# joey.net
KiCad netlist of a schematic drawn in EAGLE
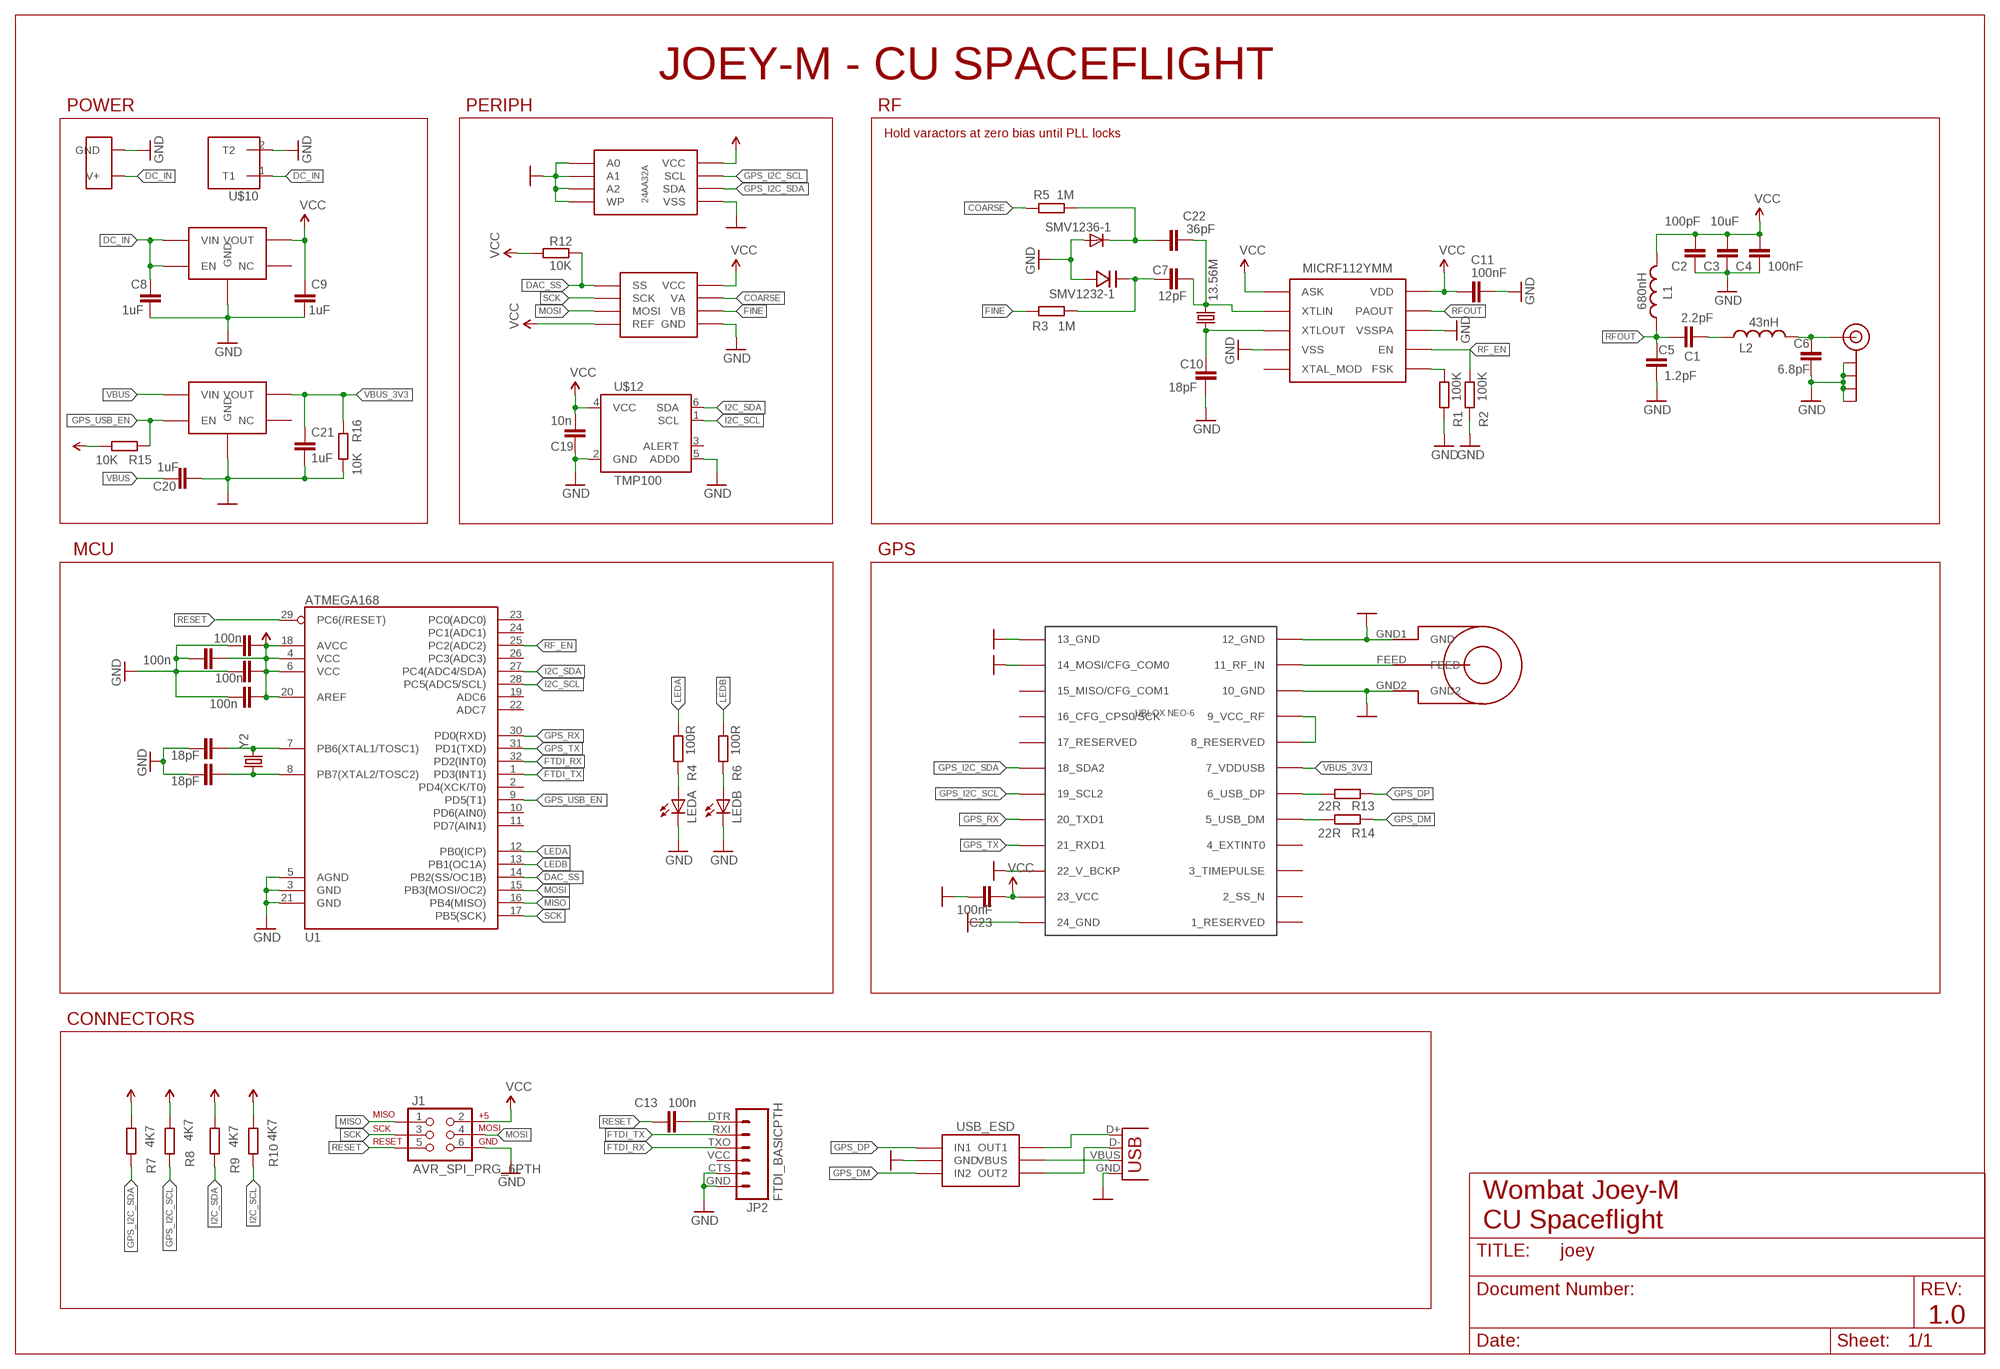
[diagram p0: schematic, sheet 1]

(export (version "E")
  (design (tool "Eeschema 10.0.6"))
  (components
    (comp (ref "C1")
      (value "2.2pF")
      (footprint "eagle-import:C0603")
      (libsource (lib "eagle-import") (part "C-EUC0603"))
    )
    (comp (ref "C2")
      (value "100pF")
      (footprint "eagle-import:C0603")
      (libsource (lib "eagle-import") (part "C-EUC0603"))
    )
    (comp (ref "C3")
      (value "10uF")
      (footprint "eagle-import:C0603")
      (libsource (lib "eagle-import") (part "C-EUC0603"))
    )
    (comp (ref "C4")
      (value "100nF")
      (footprint "eagle-import:C0603")
      (libsource (lib "eagle-import") (part "C-EUC0603"))
    )
    (comp (ref "C5")
      (value "1.2pF")
      (footprint "eagle-import:C0603")
      (libsource (lib "eagle-import") (part "C-EUC0603"))
    )
    (comp (ref "C6")
      (value "6.8pF")
      (footprint "eagle-import:C0603")
      (libsource (lib "eagle-import") (part "C-EUC0603"))
    )
    (comp (ref "C7")
      (value "12pF")
      (footprint "eagle-import:C0603")
      (libsource (lib "eagle-import") (part "C-EUC0603"))
    )
    (comp (ref "C8")
      (value "1uF")
      (footprint "eagle-import:C0603")
      (libsource (lib "eagle-import") (part "C-EUC0603"))
    )
    (comp (ref "C9")
      (value "1uF")
      (footprint "eagle-import:C0603")
      (libsource (lib "eagle-import") (part "C-EUC0603"))
    )
    (comp (ref "C10")
      (value "18pF")
      (footprint "eagle-import:C0603")
      (libsource (lib "eagle-import") (part "C-EUC0603"))
    )
    (comp (ref "C11")
      (value "100nF")
      (footprint "eagle-import:C0603")
      (libsource (lib "eagle-import") (part "C-EUC0603"))
    )
    (comp (ref "C12")
      (value "100n")
      (footprint "eagle-import:C0603")
      (libsource (lib "eagle-import") (part "C-EUC0603"))
    )
    (comp (ref "C13")
      (value "100n")
      (footprint "eagle-import:C0603")
      (libsource (lib "eagle-import") (part "C-EUC0603"))
    )
    (comp (ref "C14")
      (value "100n")
      (footprint "eagle-import:C0603")
      (libsource (lib "eagle-import") (part "C-EUC0603"))
    )
    (comp (ref "C15")
      (value "100n")
      (footprint "eagle-import:C0603")
      (libsource (lib "eagle-import") (part "C-EUC0603"))
    )
    (comp (ref "C16")
      (value "100n")
      (footprint "eagle-import:C0603")
      (libsource (lib "eagle-import") (part "C-EUC0603"))
    )
    (comp (ref "C17")
      (value "18pF")
      (footprint "eagle-import:C0603")
      (libsource (lib "eagle-import") (part "C-EUC0603"))
    )
    (comp (ref "C18")
      (value "18pF")
      (footprint "eagle-import:C0603")
      (libsource (lib "eagle-import") (part "C-EUC0603"))
    )
    (comp (ref "C19")
      (value "10n")
      (footprint "eagle-import:C0603")
      (libsource (lib "eagle-import") (part "C-EUC0603"))
    )
    (comp (ref "C20")
      (value "1uF")
      (footprint "eagle-import:C0603")
      (libsource (lib "eagle-import") (part "C-EUC0603"))
    )
    (comp (ref "C21")
      (value "1uF")
      (footprint "eagle-import:C0603")
      (libsource (lib "eagle-import") (part "C-EUC0603"))
    )
    (comp (ref "C22")
      (value "36pF")
      (footprint "eagle-import:C0603")
      (libsource (lib "eagle-import") (part "C-EUC0603"))
    )
    (comp (ref "C23")
      (value "100nF")
      (footprint "eagle-import:C0603")
      (libsource (lib "eagle-import") (part "C-EUC0603"))
    )
    (comp (ref "J1")
      (value "AVR_SPI_PRG_6PTH")
      (footprint "eagle-import:2X3")
      (libsource (lib "eagle-import") (part "AVR_SPI_PRG_6PTH"))
    )
    (comp (ref "JP2")
      (value "FTDI_BASICPTH")
      (footprint "eagle-import:FTDI_BASIC")
      (libsource (lib "eagle-import") (part "FTDI_BASICPTH"))
    )
    (comp (ref "L1")
      (value "680nH")
      (footprint "eagle-import:0603")
      (libsource (lib "eagle-import") (part "INDUCTOR0603"))
    )
    (comp (ref "L2")
      (value "43nH")
      (footprint "eagle-import:C0402")
      (libsource (lib "eagle-import") (part "INDUCTOR0402"))
    )
    (comp (ref "LEDA")
      (value "LED0603")
      (footprint "eagle-import:LED-0603")
      (libsource (lib "eagle-import") (part "LED0603"))
    )
    (comp (ref "LEDB")
      (value "LED0603")
      (footprint "eagle-import:LED-0603")
      (libsource (lib "eagle-import") (part "LED0603"))
    )
    (comp (ref "R1")
      (value "100K")
      (footprint "eagle-import:R0603")
      (libsource (lib "eagle-import") (part "R-EU_R0603"))
    )
    (comp (ref "R2")
      (value "100K")
      (footprint "eagle-import:R0603")
      (libsource (lib "eagle-import") (part "R-EU_R0603"))
    )
    (comp (ref "R3")
      (value "1M")
      (footprint "eagle-import:R0603")
      (libsource (lib "eagle-import") (part "R-EU_R0603"))
    )
    (comp (ref "R4")
      (value "100R")
      (footprint "eagle-import:R0603")
      (libsource (lib "eagle-import") (part "R-EU_R0603"))
    )
    (comp (ref "R5")
      (value "1M")
      (footprint "eagle-import:R0603")
      (libsource (lib "eagle-import") (part "R-EU_R0603"))
    )
    (comp (ref "R6")
      (value "100R")
      (footprint "eagle-import:R0603")
      (libsource (lib "eagle-import") (part "R-EU_R0603"))
    )
    (comp (ref "R7")
      (value "4K7")
      (footprint "eagle-import:R0603")
      (libsource (lib "eagle-import") (part "R-EU_R0603"))
    )
    (comp (ref "R8")
      (value "4K7")
      (footprint "eagle-import:R0603")
      (libsource (lib "eagle-import") (part "R-EU_R0603"))
    )
    (comp (ref "R9")
      (value "4K7")
      (footprint "eagle-import:R0603")
      (libsource (lib "eagle-import") (part "R-EU_R0603"))
    )
    (comp (ref "R10")
      (value "4K7")
      (footprint "eagle-import:R0603")
      (libsource (lib "eagle-import") (part "R-EU_R0603"))
    )
    (comp (ref "R12")
      (value "10K")
      (footprint "eagle-import:R0603")
      (libsource (lib "eagle-import") (part "R-EU_R0603"))
    )
    (comp (ref "R13")
      (value "22R")
      (footprint "eagle-import:R0603")
      (libsource (lib "eagle-import") (part "R-EU_R0603"))
    )
    (comp (ref "R14")
      (value "22R")
      (footprint "eagle-import:R0603")
      (libsource (lib "eagle-import") (part "R-EU_R0603"))
    )
    (comp (ref "R15")
      (value "10K")
      (footprint "eagle-import:R0603")
      (libsource (lib "eagle-import") (part "R-EU_R0603"))
    )
    (comp (ref "R16")
      (value "10K")
      (footprint "eagle-import:R0603")
      (libsource (lib "eagle-import") (part "R-EU_R0603"))
    )
    (comp (ref "SMV1232-1")
      (value "SMV1247-VARACTOR")
      (footprint "eagle-import:SMV1247-VARACTOR-SC-79")
      (libsource (lib "eagle-import") (part "SMV1247-VARACTOR"))
    )
    (comp (ref "SMV1236-1")
      (value "DIODESOD")
      (footprint "eagle-import:SOD-323")
      (libsource (lib "eagle-import") (part "DIODESOD"))
    )
    (comp (ref "U$1")
      (value "MICRF112")
      (footprint "eagle-import:MICRF112-MSOP10")
      (libsource (lib "eagle-import") (part "MICRF112"))
    )
    (comp (ref "U$2")
      (value "SARANTEL-SR1202")
      (footprint "eagle-import:SARANTEL-SR1202")
      (libsource (lib "eagle-import") (part "SARANTEL-SR1202"))
    )
    (comp (ref "U$3")
      (value "UBLOX_NEO-6")
      (footprint "eagle-import:UBLOX_NEO-6P")
      (libsource (lib "eagle-import") (part "UBLOX_NEO-6"))
    )
    (comp (ref "U$4")
      (value "ADP122AUJZ-3V3REG-5TSOT")
      (footprint "eagle-import:SOT23-5L")
      (libsource (lib "eagle-import") (part "ADP122AUJZ-3V3REG-5TSOT"))
    )
    (comp (ref "U$5")
      (value "JST_SMTSIDE")
      (footprint "eagle-import:JST_CONN_SMD")
      (libsource (lib "eagle-import") (part "JST_SMTSIDE"))
    )
    (comp (ref "U$6")
      (value "I2C_EEPROM_24AA32A")
      (footprint "eagle-import:MSOP8")
      (libsource (lib "eagle-import") (part "I2C_EEPROM_24AA32A"))
    )
    (comp (ref "U$7")
      (value "SMA_END_19-70-TGG")
      (footprint "eagle-import:SMA_END_19-70-TGG")
      (libsource (lib "eagle-import") (part "SMA_END_19-70-TGG"))
    )
    (comp (ref "U$8")
      (value "LTC2602_16BIT_DUALDAC")
      (footprint "eagle-import:MSOP8")
      (libsource (lib "eagle-import") (part "LTC2602_16BIT_DUALDAC"))
    )
    (comp (ref "U$9")
      (value "ADP122AUJZ-3V3REG-5TSOT")
      (footprint "eagle-import:SOT23-5L")
      (libsource (lib "eagle-import") (part "ADP122AUJZ-3V3REG-5TSOT"))
    )
    (comp (ref "U$10")
      (value "TE_CONN_TERMBLK")
      (footprint "eagle-import:10A_TECONN_TERMBLK")
      (libsource (lib "eagle-import") (part "TE_CONN_TERMBLK"))
    )
    (comp (ref "U$12")
      (value "TMP100")
      (footprint "eagle-import:SOT23-6")
      (libsource (lib "eagle-import") (part "TMP100"))
    )
    (comp (ref "U1")
      (value "ATMEGA168")
      (footprint "eagle-import:TQFP32-08")
      (libsource (lib "eagle-import") (part "ATMEGA168"))
    )
    (comp (ref "USB_ESD")
      (value "USB_ESD_PROT_USBLC6")
      (footprint "eagle-import:SOT23-6")
      (libsource (lib "eagle-import") (part "USB_ESD_PROT_USBLC6"))
    )
    (comp (ref "X1")
      (value "USB-MICROB")
      (footprint "eagle-import:USB-MICROB")
      (libsource (lib "eagle-import") (part "USB-MICROB"))
    )
    (comp (ref "Y1")
      (value "13.56M")
      (footprint "eagle-import:CRYSTAL-SMD-5X3")
      (libsource (lib "eagle-import") (part "CRYSTAL5X3"))
    )
    (comp (ref "Y2")
      (value "CRYSTAL5X3")
      (footprint "eagle-import:CRYSTAL-SMD-5X3")
      (libsource (lib "eagle-import") (part "CRYSTAL5X3"))
    )
  )
  (nets
    (net (code "1") (name "COARSE") (class "Default")
      (node (ref "R5") (pin "1") (pinfunction "1_1") (pintype "passive"))
      (node (ref "U$8") (pin "8") (pinfunction "VA_8") (pintype "bidirectional"))
    )
    (net (code "2") (name "DAC_SS") (class "Default")
      (node (ref "R12") (pin "2") (pinfunction "2_2") (pintype "passive"))
      (node (ref "U$8") (pin "1") (pinfunction "SS_1") (pintype "bidirectional"))
      (node (ref "U1") (pin "14") (pinfunction "PB2(SS/OC1B)_14") (pintype "bidirectional"))
    )
    (net (code "3") (name "DC_IN") (class "Default")
      (node (ref "C8") (pin "2") (pinfunction "2_2") (pintype "passive"))
      (node (ref "U$10") (pin "1") (pinfunction "T1_1") (pintype "bidirectional"))
      (node (ref "U$4") (pin "1") (pinfunction "VIN_1") (pintype "bidirectional"))
      (node (ref "U$4") (pin "3") (pinfunction "EN_3") (pintype "bidirectional"))
      (node (ref "U$5") (pin "VBATT") (pinfunction "V+_VBATT") (pintype "bidirectional"))
    )
    (net (code "4") (name "FINE") (class "Default")
      (node (ref "R3") (pin "2") (pinfunction "2_2") (pintype "passive"))
      (node (ref "U$8") (pin "5") (pinfunction "VB_5") (pintype "bidirectional"))
    )
    (net (code "5") (name "FTDI_RX") (class "Default")
      (node (ref "JP2") (pin "TXO") (pinfunction "3_TXO") (pintype "passive"))
      (node (ref "U1") (pin "32") (pinfunction "PD2(INT0)_32") (pintype "bidirectional"))
    )
    (net (code "6") (name "FTDI_TX") (class "Default")
      (node (ref "JP2") (pin "RXI") (pinfunction "2_RXI") (pintype "passive"))
      (node (ref "U1") (pin "1") (pinfunction "PD3(INT1)_1") (pintype "bidirectional"))
    )
    (net (code "7") (name "GND") (class "Default")
      (node (ref "C10") (pin "1") (pinfunction "1_1") (pintype "passive"))
      (node (ref "C11") (pin "1") (pinfunction "1_1") (pintype "passive"))
      (node (ref "C12") (pin "2") (pinfunction "2_2") (pintype "passive"))
      (node (ref "C14") (pin "1") (pinfunction "1_1") (pintype "passive"))
      (node (ref "C15") (pin "1") (pinfunction "1_1") (pintype "passive"))
      (node (ref "C16") (pin "1") (pinfunction "1_1") (pintype "passive"))
      (node (ref "C17") (pin "2") (pinfunction "2_2") (pintype "passive"))
      (node (ref "C18") (pin "2") (pinfunction "2_2") (pintype "passive"))
      (node (ref "C19") (pin "1") (pinfunction "1_1") (pintype "passive"))
      (node (ref "C2") (pin "1") (pinfunction "1_1") (pintype "passive"))
      (node (ref "C20") (pin "1") (pinfunction "1_1") (pintype "passive"))
      (node (ref "C21") (pin "1") (pinfunction "1_1") (pintype "passive"))
      (node (ref "C23") (pin "1") (pinfunction "1_1") (pintype "passive"))
      (node (ref "C3") (pin "1") (pinfunction "1_1") (pintype "passive"))
      (node (ref "C4") (pin "1") (pinfunction "1_1") (pintype "passive"))
      (node (ref "C5") (pin "1") (pinfunction "1_1") (pintype "passive"))
      (node (ref "C6") (pin "1") (pinfunction "1_1") (pintype "passive"))
      (node (ref "C8") (pin "1") (pinfunction "1_1") (pintype "passive"))
      (node (ref "C9") (pin "1") (pinfunction "1_1") (pintype "passive"))
      (node (ref "J1") (pin "6") (pinfunction "6_6") (pintype "passive"))
      (node (ref "JP2") (pin "CTS") (pinfunction "5_CTS") (pintype "passive"))
      (node (ref "JP2") (pin "GND") (pinfunction "6_GND") (pintype "passive"))
      (node (ref "LEDA") (pin "C") (pinfunction "C_C") (pintype "passive"))
      (node (ref "LEDB") (pin "C") (pinfunction "C_C") (pintype "passive"))
      (node (ref "R1") (pin "1") (pinfunction "1_1") (pintype "passive"))
      (node (ref "R16") (pin "2") (pinfunction "2_2") (pintype "passive"))
      (node (ref "R2") (pin "1") (pinfunction "1_1") (pintype "passive"))
      (node (ref "SMV1232-1") (pin "AN") (pinfunction "ANODE_AN") (pintype "bidirectional"))
      (node (ref "SMV1236-1") (pin "2") (pinfunction "A_2") (pintype "passive"))
      (node (ref "U$1") (pin "VSS") (pinfunction "VSS_VSS") (pintype "bidirectional"))
      (node (ref "U$1") (pin "VSSPA") (pinfunction "VSSPA_VSSPA") (pintype "bidirectional"))
      (node (ref "U$10") (pin "2") (pinfunction "T2_2") (pintype "bidirectional"))
      (node (ref "U$12") (pin "2") (pinfunction "GND_2") (pintype "bidirectional"))
      (node (ref "U$12") (pin "5") (pinfunction "ADD0_5") (pintype "bidirectional"))
      (node (ref "U$2") (pin "GND1") (pinfunction "GND_GND1") (pintype "bidirectional"))
      (node (ref "U$2") (pin "GND2") (pinfunction "GND2_GND2") (pintype "bidirectional"))
      (node (ref "U$3") (pin "10_GND") (pinfunction "10_GND_10_GND") (pintype "bidirectional"))
      (node (ref "U$3") (pin "12_GND") (pinfunction "12_GND_12_GND") (pintype "bidirectional"))
      (node (ref "U$3") (pin "13_GND") (pinfunction "13_GND_13_GND") (pintype "bidirectional"))
      (node (ref "U$3") (pin "14_MOSI/CFG_COM0") (pinfunction "14_MOSI/CFG_COM0_14_MOSI/CFG_COM0") (pintype "bidirectional"))
      (node (ref "U$3") (pin "22_V_BCKP") (pinfunction "22_V_BCKP_22_V_BCKP") (pintype "bidirectional"))
      (node (ref "U$3") (pin "24_GND") (pinfunction "24_GND_24_GND") (pintype "bidirectional"))
      (node (ref "U$4") (pin "2") (pinfunction "GND_2") (pintype "bidirectional"))
      (node (ref "U$5") (pin "GND") (pinfunction "GND_GND") (pintype "bidirectional"))
      (node (ref "U$6") (pin "1") (pinfunction "A0_1") (pintype "bidirectional"))
      (node (ref "U$6") (pin "2") (pinfunction "A1_2") (pintype "bidirectional"))
      (node (ref "U$6") (pin "3") (pinfunction "A2_3") (pintype "bidirectional"))
      (node (ref "U$6") (pin "4") (pinfunction "VSS_4") (pintype "bidirectional"))
      (node (ref "U$6") (pin "7") (pinfunction "WP_7") (pintype "bidirectional"))
      (node (ref "U$7") (pin "GND1") (pinfunction "GND_GND1") (pintype "bidirectional"))
      (node (ref "U$7") (pin "GND2") (pinfunction "GND_GND2") (pintype "bidirectional"))
      (node (ref "U$7") (pin "GND3") (pinfunction "GND_GND3") (pintype "bidirectional"))
      (node (ref "U$7") (pin "GND4") (pinfunction "GND_GND4") (pintype "bidirectional"))
      (node (ref "U$8") (pin "7") (pinfunction "GND_7") (pintype "bidirectional"))
      (node (ref "U$9") (pin "2") (pinfunction "GND_2") (pintype "bidirectional"))
      (node (ref "U1") (pin "21") (pinfunction "GND_21") (pintype "bidirectional"))
      (node (ref "U1") (pin "3") (pinfunction "GND_3") (pintype "bidirectional"))
      (node (ref "U1") (pin "5") (pinfunction "AGND_5") (pintype "bidirectional"))
      (node (ref "USB_ESD") (pin "2") (pinfunction "GND_2") (pintype "bidirectional"))
      (node (ref "X1") (pin "GND") (pinfunction "GND_GND") (pintype "bidirectional"))
    )
    (net (code "8") (name "GPS_DM") (class "Default")
      (node (ref "R14") (pin "1") (pinfunction "1_1") (pintype "passive"))
      (node (ref "USB_ESD") (pin "3") (pinfunction "IN2_3") (pintype "bidirectional"))
    )
    (net (code "9") (name "GPS_DP") (class "Default")
      (node (ref "R13") (pin "1") (pinfunction "1_1") (pintype "passive"))
      (node (ref "USB_ESD") (pin "1") (pinfunction "IN1_1") (pintype "bidirectional"))
    )
    (net (code "10") (name "GPS_I2C_SCL") (class "Default")
      (node (ref "R8") (pin "1") (pinfunction "1_1") (pintype "passive"))
      (node (ref "U$3") (pin "19_SCL2") (pinfunction "19_SCL2_19_SCL2") (pintype "bidirectional"))
      (node (ref "U$6") (pin "6") (pinfunction "SCL_6") (pintype "bidirectional"))
    )
    (net (code "11") (name "GPS_I2C_SDA") (class "Default")
      (node (ref "R7") (pin "1") (pinfunction "1_1") (pintype "passive"))
      (node (ref "U$3") (pin "18_SDA2") (pinfunction "18_SDA2_18_SDA2") (pintype "bidirectional"))
      (node (ref "U$6") (pin "5") (pinfunction "SDA_5") (pintype "bidirectional"))
    )
    (net (code "12") (name "GPS_RX") (class "Default")
      (node (ref "U$3") (pin "20_TXD1") (pinfunction "20_TXD1_20_TXD1") (pintype "bidirectional"))
      (node (ref "U1") (pin "30") (pinfunction "PD0(RXD)_30") (pintype "bidirectional"))
    )
    (net (code "13") (name "GPS_TX") (class "Default")
      (node (ref "U$3") (pin "21_RXD1") (pinfunction "21_RXD1_21_RXD1") (pintype "bidirectional"))
      (node (ref "U1") (pin "31") (pinfunction "PD1(TXD)_31") (pintype "bidirectional"))
    )
    (net (code "14") (name "GPS_USB_EN") (class "Default")
      (node (ref "R15") (pin "1") (pinfunction "1_1") (pintype "passive"))
      (node (ref "U$9") (pin "3") (pinfunction "EN_3") (pintype "bidirectional"))
      (node (ref "U1") (pin "9") (pinfunction "PD5(T1)_9") (pintype "bidirectional"))
    )
    (net (code "15") (name "I2C_SCL") (class "Default")
      (node (ref "R10") (pin "1") (pinfunction "1_1") (pintype "passive"))
      (node (ref "U$12") (pin "1") (pinfunction "SCL_1") (pintype "bidirectional"))
      (node (ref "U1") (pin "28") (pinfunction "PC5(ADC5/SCL)_28") (pintype "bidirectional"))
    )
    (net (code "16") (name "I2C_SDA") (class "Default")
      (node (ref "R9") (pin "1") (pinfunction "1_1") (pintype "passive"))
      (node (ref "U$12") (pin "6") (pinfunction "SDA_6") (pintype "bidirectional"))
      (node (ref "U1") (pin "27") (pinfunction "PC4(ADC4/SDA)_27") (pintype "bidirectional"))
    )
    (net (code "17") (name "LEDA") (class "Default")
      (node (ref "R4") (pin "2") (pinfunction "2_2") (pintype "passive"))
      (node (ref "U1") (pin "12") (pinfunction "PB0(ICP)_12") (pintype "bidirectional"))
    )
    (net (code "18") (name "LEDB") (class "Default")
      (node (ref "R6") (pin "2") (pinfunction "2_2") (pintype "passive"))
      (node (ref "U1") (pin "13") (pinfunction "PB1(OC1A)_13") (pintype "bidirectional"))
    )
    (net (code "19") (name "MISO") (class "Default")
      (node (ref "J1") (pin "1") (pinfunction "1_1") (pintype "passive"))
      (node (ref "U1") (pin "16") (pinfunction "PB4(MISO)_16") (pintype "bidirectional"))
    )
    (net (code "20") (name "MOSI") (class "Default")
      (node (ref "J1") (pin "4") (pinfunction "4_4") (pintype "passive"))
      (node (ref "U$8") (pin "3") (pinfunction "MOSI_3") (pintype "bidirectional"))
      (node (ref "U1") (pin "15") (pinfunction "PB3(MOSI/OC2)_15") (pintype "bidirectional"))
    )
    (net (code "21") (name "Net-(C1-Pad2)") (class "Default")
      (node (ref "C1") (pin "2") (pinfunction "2_2") (pintype "passive"))
      (node (ref "L2") (pin "1") (pinfunction "1_1") (pintype "passive"))
    )
    (net (code "22") (name "Net-(C10-Pad2)") (class "Default")
      (node (ref "C10") (pin "2") (pinfunction "2_2") (pintype "passive"))
      (node (ref "U$1") (pin "XTLOUT") (pinfunction "XTLOUT_XTLOUT") (pintype "bidirectional"))
      (node (ref "Y1") (pin "1") (pinfunction "1_1") (pintype "passive"))
    )
    (net (code "23") (name "Net-(JP2-1)") (class "Default")
      (node (ref "C13") (pin "2") (pinfunction "2_2") (pintype "passive"))
      (node (ref "JP2") (pin "DTR") (pinfunction "1_DTR") (pintype "passive"))
    )
    (net (code "24") (name "Net-(LEDA-PadA)") (class "Default")
      (node (ref "LEDA") (pin "A") (pinfunction "A_A") (pintype "passive"))
      (node (ref "R4") (pin "1") (pinfunction "1_1") (pintype "passive"))
    )
    (net (code "25") (name "Net-(LEDB-PadA)") (class "Default")
      (node (ref "LEDB") (pin "A") (pinfunction "A_A") (pintype "passive"))
      (node (ref "R6") (pin "1") (pinfunction "1_1") (pintype "passive"))
    )
    (net (code "26") (name "Net-(R1-Pad2)") (class "Default")
      (node (ref "R1") (pin "2") (pinfunction "2_2") (pintype "passive"))
      (node (ref "U$1") (pin "FSK") (pinfunction "FSK_FSK") (pintype "bidirectional"))
    )
    (net (code "27") (name "Net-(R13-Pad2)") (class "Default")
      (node (ref "R13") (pin "2") (pinfunction "2_2") (pintype "passive"))
      (node (ref "U$3") (pin "6_USB_DP") (pinfunction "6_USB_DP_6_USB_DP") (pintype "bidirectional"))
    )
    (net (code "28") (name "Net-(R14-Pad2)") (class "Default")
      (node (ref "R14") (pin "2") (pinfunction "2_2") (pintype "passive"))
      (node (ref "U$3") (pin "5_USB_DM") (pinfunction "5_USB_DM_5_USB_DM") (pintype "bidirectional"))
    )
    (net (code "29") (name "Net-(SMV1232-1-CATHODE)") (class "Default")
      (node (ref "C7") (pin "1") (pinfunction "1_1") (pintype "passive"))
      (node (ref "R3") (pin "1") (pinfunction "1_1") (pintype "passive"))
      (node (ref "SMV1232-1") (pin "CAT") (pinfunction "CATHODE_CAT") (pintype "bidirectional"))
    )
    (net (code "30") (name "Net-(SMV1236-1-C)") (class "Default")
      (node (ref "C22") (pin "1") (pinfunction "1_1") (pintype "passive"))
      (node (ref "R5") (pin "2") (pinfunction "2_2") (pintype "passive"))
      (node (ref "SMV1236-1") (pin "1") (pinfunction "C_1") (pintype "passive"))
    )
    (net (code "31") (name "Net-(U$2-PadFEED)") (class "Default")
      (node (ref "U$2") (pin "FEED") (pinfunction "FEED_FEED") (pintype "bidirectional"))
      (node (ref "U$3") (pin "11_RF_IN") (pinfunction "11_RF_IN_11_RF_IN") (pintype "bidirectional"))
    )
    (net (code "32") (name "Net-(U$3-Pad8_RESERVED)") (class "Default")
      (node (ref "U$3") (pin "8_RESERVED") (pinfunction "8_RESERVED_8_RESERVED") (pintype "bidirectional"))
      (node (ref "U$3") (pin "9_VCC_RF") (pinfunction "9_VCC_RF_9_VCC_RF") (pintype "bidirectional"))
    )
    (net (code "33") (name "Net-(U$7-SIGNAL)") (class "Default")
      (node (ref "C6") (pin "2") (pinfunction "2_2") (pintype "passive"))
      (node (ref "L2") (pin "2") (pinfunction "2_2") (pintype "passive"))
      (node (ref "U$7") (pin "RF") (pinfunction "SIGNAL_RF") (pintype "bidirectional"))
    )
    (net (code "34") (name "Net-(U1-PB6(XTAL1{slash}TOSC1))") (class "Default")
      (node (ref "C17") (pin "1") (pinfunction "1_1") (pintype "passive"))
      (node (ref "U1") (pin "7") (pinfunction "PB6(XTAL1/TOSC1)_7") (pintype "bidirectional"))
      (node (ref "Y2") (pin "3") (pinfunction "2_3") (pintype "passive"))
    )
    (net (code "35") (name "Net-(U1-PB7(XTAL2{slash}TOSC2))") (class "Default")
      (node (ref "C18") (pin "1") (pinfunction "1_1") (pintype "passive"))
      (node (ref "U1") (pin "8") (pinfunction "PB7(XTAL2/TOSC2)_8") (pintype "bidirectional"))
      (node (ref "Y2") (pin "1") (pinfunction "1_1") (pintype "passive"))
    )
    (net (code "36") (name "Net-(USB_ESD-OUT1)") (class "Default")
      (node (ref "USB_ESD") (pin "6") (pinfunction "OUT1_6") (pintype "bidirectional"))
      (node (ref "X1") (pin "D+") (pinfunction "D+_D+") (pintype "bidirectional"))
    )
    (net (code "37") (name "Net-(USB_ESD-OUT2)") (class "Default")
      (node (ref "USB_ESD") (pin "4") (pinfunction "OUT2_4") (pintype "bidirectional"))
      (node (ref "X1") (pin "D-") (pinfunction "D-_D-") (pintype "bidirectional"))
    )
    (net (code "38") (name "Net-(Y1-2)") (class "Default")
      (node (ref "C22") (pin "2") (pinfunction "2_2") (pintype "passive"))
      (node (ref "C7") (pin "2") (pinfunction "2_2") (pintype "passive"))
      (node (ref "U$1") (pin "XTLIN") (pinfunction "XTLIN_XTLIN") (pintype "bidirectional"))
      (node (ref "Y1") (pin "3") (pinfunction "2_3") (pintype "passive"))
    )
    (net (code "39") (name "RESET") (class "Default")
      (node (ref "C13") (pin "1") (pinfunction "1_1") (pintype "passive"))
      (node (ref "J1") (pin "5") (pinfunction "5_5") (pintype "passive"))
      (node (ref "U1") (pin "29") (pinfunction "PC6(/RESET)_29") (pintype "bidirectional"))
    )
    (net (code "40") (name "RFOUT") (class "Default")
      (node (ref "C1") (pin "1") (pinfunction "1_1") (pintype "passive"))
      (node (ref "C5") (pin "2") (pinfunction "2_2") (pintype "passive"))
      (node (ref "L1") (pin "1") (pinfunction "1_1") (pintype "passive"))
      (node (ref "U$1") (pin "PAOUT") (pinfunction "PAOUT_PAOUT") (pintype "bidirectional"))
    )
    (net (code "41") (name "RF_EN") (class "Default")
      (node (ref "R2") (pin "2") (pinfunction "2_2") (pintype "passive"))
      (node (ref "U$1") (pin "EN") (pinfunction "EN_EN") (pintype "bidirectional"))
      (node (ref "U1") (pin "25") (pinfunction "PC2(ADC2)_25") (pintype "bidirectional"))
    )
    (net (code "42") (name "SCK") (class "Default")
      (node (ref "J1") (pin "3") (pinfunction "3_3") (pintype "passive"))
      (node (ref "U$8") (pin "2") (pinfunction "SCK_2") (pintype "bidirectional"))
      (node (ref "U1") (pin "17") (pinfunction "PB5(SCK)_17") (pintype "bidirectional"))
    )
    (net (code "43") (name "VBUS") (class "Default")
      (node (ref "C20") (pin "2") (pinfunction "2_2") (pintype "passive"))
      (node (ref "U$9") (pin "1") (pinfunction "VIN_1") (pintype "bidirectional"))
      (node (ref "USB_ESD") (pin "5") (pinfunction "VBUS_5") (pintype "bidirectional"))
      (node (ref "X1") (pin "VBUS") (pinfunction "VBUS_VBUS") (pintype "bidirectional"))
    )
    (net (code "44") (name "VBUS_3V3") (class "Default")
      (node (ref "C21") (pin "2") (pinfunction "2_2") (pintype "passive"))
      (node (ref "R16") (pin "1") (pinfunction "1_1") (pintype "passive"))
      (node (ref "U$3") (pin "7_VDDUSB") (pinfunction "7_VDDUSB_7_VDDUSB") (pintype "bidirectional"))
      (node (ref "U$9") (pin "5") (pinfunction "VOUT_5") (pintype "bidirectional"))
    )
    (net (code "45") (name "VCC") (class "Default")
      (node (ref "C11") (pin "2") (pinfunction "2_2") (pintype "passive"))
      (node (ref "C12") (pin "1") (pinfunction "1_1") (pintype "passive"))
      (node (ref "C14") (pin "2") (pinfunction "2_2") (pintype "passive"))
      (node (ref "C15") (pin "2") (pinfunction "2_2") (pintype "passive"))
      (node (ref "C16") (pin "2") (pinfunction "2_2") (pintype "passive"))
      (node (ref "C19") (pin "2") (pinfunction "2_2") (pintype "passive"))
      (node (ref "C2") (pin "2") (pinfunction "2_2") (pintype "passive"))
      (node (ref "C23") (pin "2") (pinfunction "2_2") (pintype "passive"))
      (node (ref "C3") (pin "2") (pinfunction "2_2") (pintype "passive"))
      (node (ref "C4") (pin "2") (pinfunction "2_2") (pintype "passive"))
      (node (ref "C9") (pin "2") (pinfunction "2_2") (pintype "passive"))
      (node (ref "J1") (pin "2") (pinfunction "2_2") (pintype "passive"))
      (node (ref "L1") (pin "2") (pinfunction "2_2") (pintype "passive"))
      (node (ref "R10") (pin "2") (pinfunction "2_2") (pintype "passive"))
      (node (ref "R12") (pin "1") (pinfunction "1_1") (pintype "passive"))
      (node (ref "R15") (pin "2") (pinfunction "2_2") (pintype "passive"))
      (node (ref "R7") (pin "2") (pinfunction "2_2") (pintype "passive"))
      (node (ref "R8") (pin "2") (pinfunction "2_2") (pintype "passive"))
      (node (ref "R9") (pin "2") (pinfunction "2_2") (pintype "passive"))
      (node (ref "U$1") (pin "ASK") (pinfunction "ASK_ASK") (pintype "bidirectional"))
      (node (ref "U$1") (pin "VDD") (pinfunction "VDD_VDD") (pintype "bidirectional"))
      (node (ref "U$12") (pin "4") (pinfunction "VCC_4") (pintype "bidirectional"))
      (node (ref "U$3") (pin "23_VCC") (pinfunction "23_VCC_23_VCC") (pintype "bidirectional"))
      (node (ref "U$4") (pin "5") (pinfunction "VOUT_5") (pintype "bidirectional"))
      (node (ref "U$6") (pin "8") (pinfunction "VCC_8") (pintype "bidirectional"))
      (node (ref "U$8") (pin "4") (pinfunction "REF_4") (pintype "bidirectional"))
      (node (ref "U$8") (pin "6") (pinfunction "VCC_6") (pintype "bidirectional"))
      (node (ref "U1") (pin "18") (pinfunction "AVCC_18") (pintype "bidirectional"))
      (node (ref "U1") (pin "20") (pinfunction "AREF_20") (pintype "bidirectional"))
      (node (ref "U1") (pin "4") (pinfunction "VCC_4") (pintype "bidirectional"))
      (node (ref "U1") (pin "6") (pinfunction "VCC_6") (pintype "bidirectional"))
    )
    (net (code "46") (name "unconnected-(JP2-4-PadVCC)") (class "Default")
      (node (ref "JP2") (pin "VCC") (pinfunction "4_VCC") (pintype "passive"))
    )
    (net (code "47") (name "unconnected-(U$1-PadXTAL_MOD)") (class "Default")
      (node (ref "U$1") (pin "XTAL_MOD") (pinfunction "XTAL_MOD_XTAL_MOD") (pintype "bidirectional"))
    )
    (net (code "48") (name "unconnected-(U$3-Pad1_RESERVED)") (class "Default")
      (node (ref "U$3") (pin "1_RESERVED") (pinfunction "1_RESERVED_1_RESERVED") (pintype "bidirectional"))
    )
    (net (code "49") (name "unconnected-(U$3-Pad2_SS_N)") (class "Default")
      (node (ref "U$3") (pin "2_SS_N") (pinfunction "2_SS_N_2_SS_N") (pintype "bidirectional"))
    )
    (net (code "50") (name "unconnected-(U$3-Pad3_TIMEPULSE)") (class "Default")
      (node (ref "U$3") (pin "3_TIMEPULSE") (pinfunction "3_TIMEPULSE_3_TIMEPULSE") (pintype "bidirectional"))
    )
    (net (code "51") (name "unconnected-(U$3-Pad4_EXTINT0)") (class "Default")
      (node (ref "U$3") (pin "4_EXTINT0") (pinfunction "4_EXTINT0_4_EXTINT0") (pintype "bidirectional"))
    )
    (net (code "52") (name "unconnected-(U$3-Pad15_MISO{slash}CFG_COM1)") (class "Default")
      (node (ref "U$3") (pin "15_MISO/CFG_COM1") (pinfunction "15_MISO/CFG_COM1_15_MISO/CFG_COM1") (pintype "bidirectional"))
    )
    (net (code "53") (name "unconnected-(U$3-Pad16_CFG_CPS0{slash}SCK)") (class "Default")
      (node (ref "U$3") (pin "16_CFG_CPS0/SCK") (pinfunction "16_CFG_CPS0/SCK_16_CFG_CPS0/SCK") (pintype "bidirectional"))
    )
    (net (code "54") (name "unconnected-(U$3-Pad17_RESERVED)") (class "Default")
      (node (ref "U$3") (pin "17_RESERVED") (pinfunction "17_RESERVED_17_RESERVED") (pintype "bidirectional"))
    )
    (net (code "55") (name "unconnected-(U$4-NC-Pad4)") (class "Default")
      (node (ref "U$4") (pin "4") (pinfunction "NC_4") (pintype "bidirectional"))
    )
    (net (code "56") (name "unconnected-(U$9-NC-Pad4)") (class "Default")
      (node (ref "U$9") (pin "4") (pinfunction "NC_4") (pintype "bidirectional"))
    )
    (net (code "57") (name "unconnected-(U$12-ALERT-Pad3)") (class "Default")
      (node (ref "U$12") (pin "3") (pinfunction "ALERT_3") (pintype "bidirectional"))
    )
    (net (code "58") (name "unconnected-(U1-ADC6-Pad19)") (class "Default")
      (node (ref "U1") (pin "19") (pinfunction "ADC6_19") (pintype "bidirectional"))
    )
    (net (code "59") (name "unconnected-(U1-ADC7-Pad22)") (class "Default")
      (node (ref "U1") (pin "22") (pinfunction "ADC7_22") (pintype "bidirectional"))
    )
    (net (code "60") (name "unconnected-(U1-PC0(ADC0)-Pad23)") (class "Default")
      (node (ref "U1") (pin "23") (pinfunction "PC0(ADC0)_23") (pintype "bidirectional"))
    )
    (net (code "61") (name "unconnected-(U1-PC1(ADC1)-Pad24)") (class "Default")
      (node (ref "U1") (pin "24") (pinfunction "PC1(ADC1)_24") (pintype "bidirectional"))
    )
    (net (code "62") (name "unconnected-(U1-PC3(ADC3)-Pad26)") (class "Default")
      (node (ref "U1") (pin "26") (pinfunction "PC3(ADC3)_26") (pintype "bidirectional"))
    )
    (net (code "63") (name "unconnected-(U1-PD4(XCK{slash}T0)-Pad2)") (class "Default")
      (node (ref "U1") (pin "2") (pinfunction "PD4(XCK/T0)_2") (pintype "bidirectional"))
    )
    (net (code "64") (name "unconnected-(U1-PD6(AIN0)-Pad10)") (class "Default")
      (node (ref "U1") (pin "10") (pinfunction "PD6(AIN0)_10") (pintype "bidirectional"))
    )
    (net (code "65") (name "unconnected-(U1-PD7(AIN1)-Pad11)") (class "Default")
      (node (ref "U1") (pin "11") (pinfunction "PD7(AIN1)_11") (pintype "bidirectional"))
    )
  )
)
